# camera.net
KiCad netlist of a schematic drawn in EAGLE
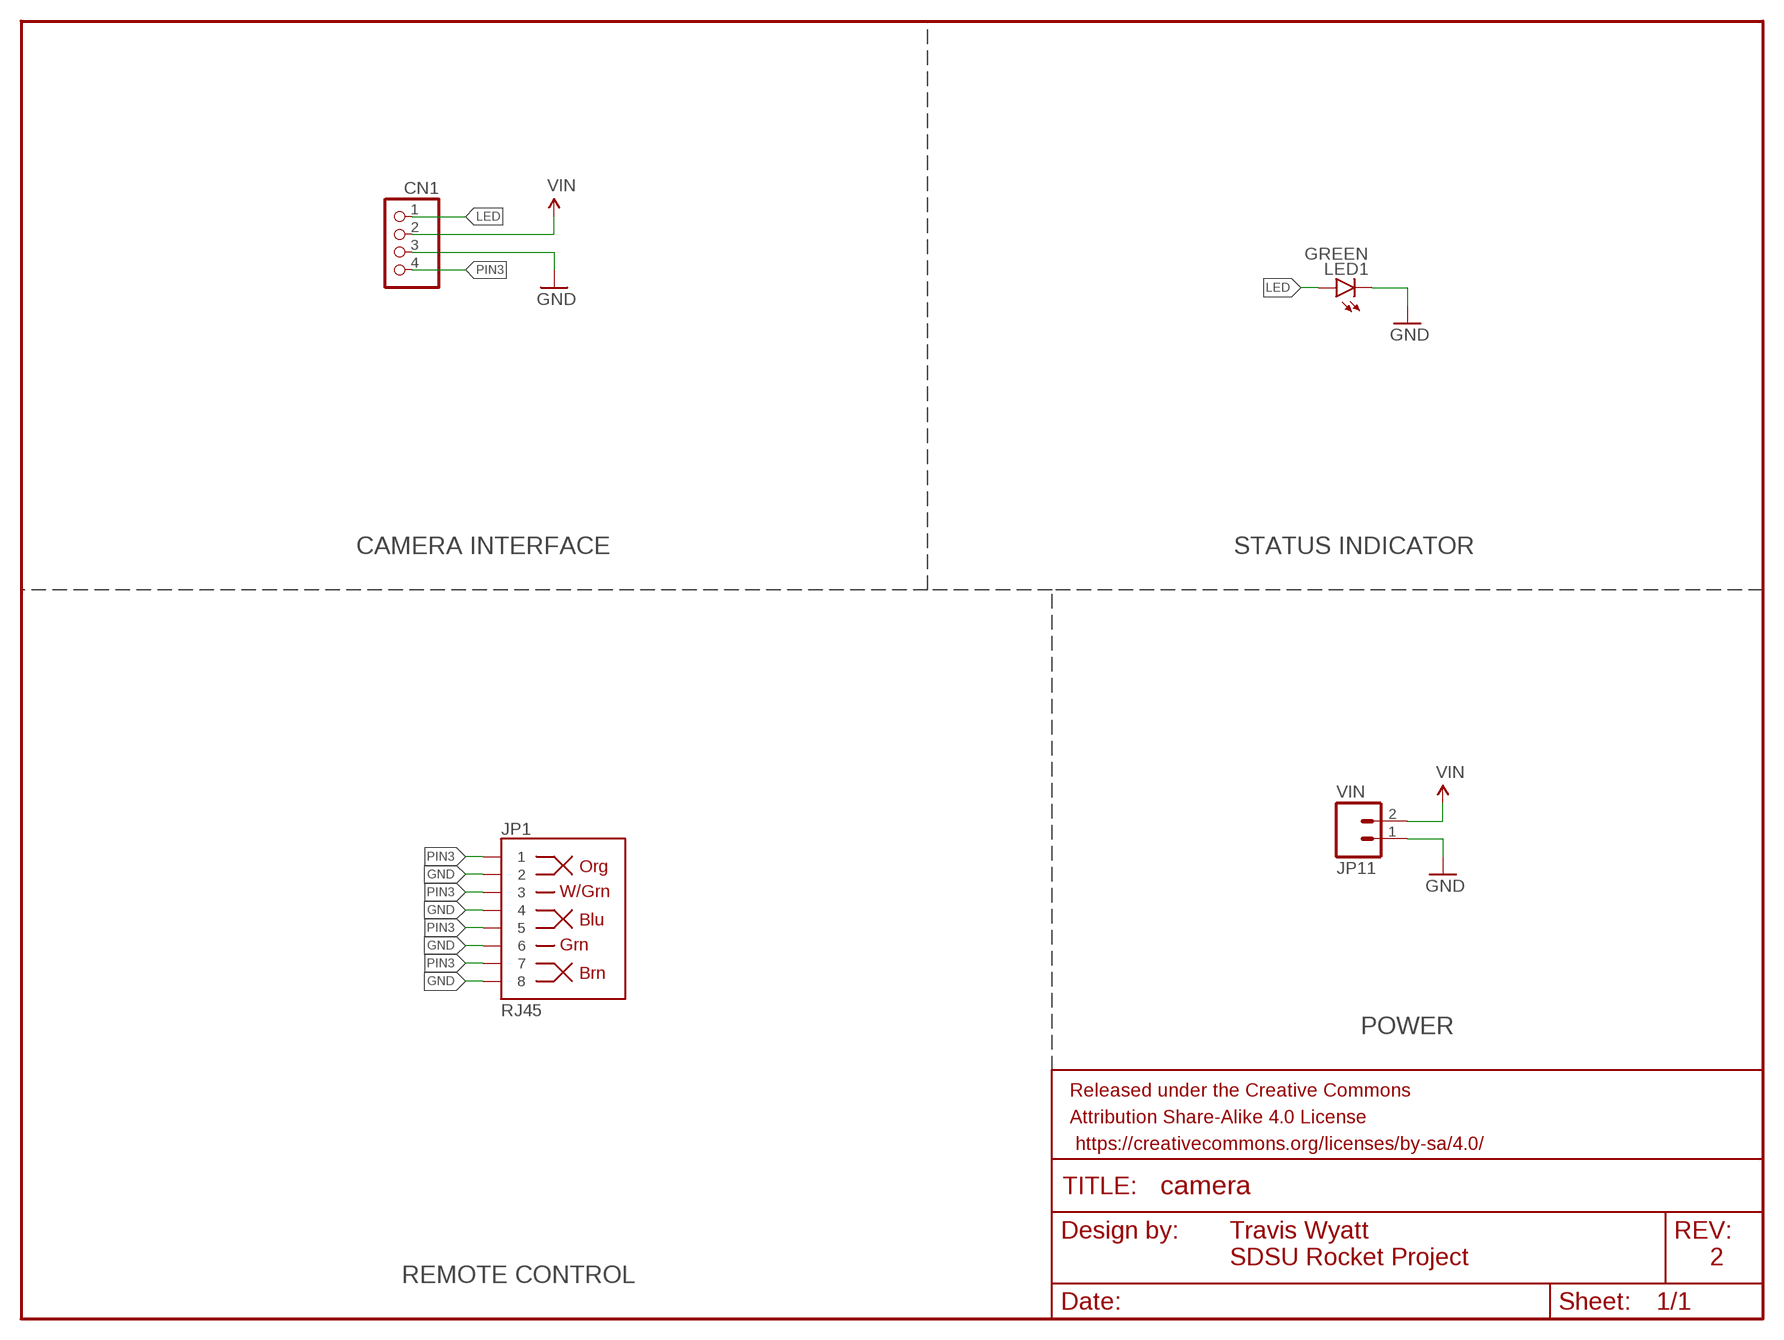
[diagram p0: schematic, sheet 1]

(export (version "E")
  (design (tool "Eeschema 10.0.6"))
  (components
    (comp (ref "CN1")
      (value "JST_4PIN")
      (footprint "eagle-import:JSTPH4")
      (libsource (lib "eagle-import") (part "JST_4PIN"))
    )
    (comp (ref "FRAME1")
      (value "FRAME-LETTER")
      (footprint "eagle-import:CREATIVE_COMMONS")
      (fields (field (name "DESIGNER") "NAME"))
      (libsource (lib "eagle-import") (part "FRAME-LETTER"))
    )
    (comp (ref "JP1")
      (value "RJ45")
      (footprint "eagle-import:RJ45-8")
      (libsource (lib "eagle-import") (part "RJ45-8PTH"))
    )
    (comp (ref "JP11")
      (value "VIN")
      (footprint "eagle-import:JST-2-SMD")
      (libsource (lib "eagle-import") (part "M02-JST-2MM-SMT"))
    )
    (comp (ref "LED1")
      (value "GREEN")
      (footprint "eagle-import:LED-0603")
      (libsource (lib "eagle-import") (part "LED-GREEN0603"))
    )
  )
  (nets
    (net (code "1") (name "GND") (class "Default")
      (node (ref "CN1") (pin "3") (pinfunction "3_3") (pintype "passive"))
      (node (ref "JP1") (pin "2") (pinfunction "2_2") (pintype "bidirectional"))
      (node (ref "JP1") (pin "4") (pinfunction "4_4") (pintype "bidirectional"))
      (node (ref "JP1") (pin "6") (pinfunction "6_6") (pintype "bidirectional"))
      (node (ref "JP1") (pin "8") (pinfunction "8_8") (pintype "bidirectional"))
      (node (ref "JP11") (pin "1") (pinfunction "2_1") (pintype "passive"))
      (node (ref "LED1") (pin "C") (pinfunction "C_C") (pintype "passive"))
    )
    (net (code "2") (name "LED") (class "Default")
      (node (ref "CN1") (pin "1") (pinfunction "1_1") (pintype "passive"))
      (node (ref "LED1") (pin "A") (pinfunction "A_A") (pintype "passive"))
    )
    (net (code "3") (name "PIN3") (class "Default")
      (node (ref "CN1") (pin "4") (pinfunction "4_4") (pintype "passive"))
      (node (ref "JP1") (pin "1") (pinfunction "1_1") (pintype "bidirectional"))
      (node (ref "JP1") (pin "3") (pinfunction "3_3") (pintype "bidirectional"))
      (node (ref "JP1") (pin "5") (pinfunction "5_5") (pintype "bidirectional"))
      (node (ref "JP1") (pin "7") (pinfunction "7_7") (pintype "bidirectional"))
    )
    (net (code "4") (name "VIN") (class "Default")
      (node (ref "CN1") (pin "2") (pinfunction "2_2") (pintype "passive"))
      (node (ref "JP11") (pin "2") (pinfunction "1_2") (pintype "passive"))
    )
  )
)
